# GPS.net
KiCad netlist of a schematic drawn in Altium Designer
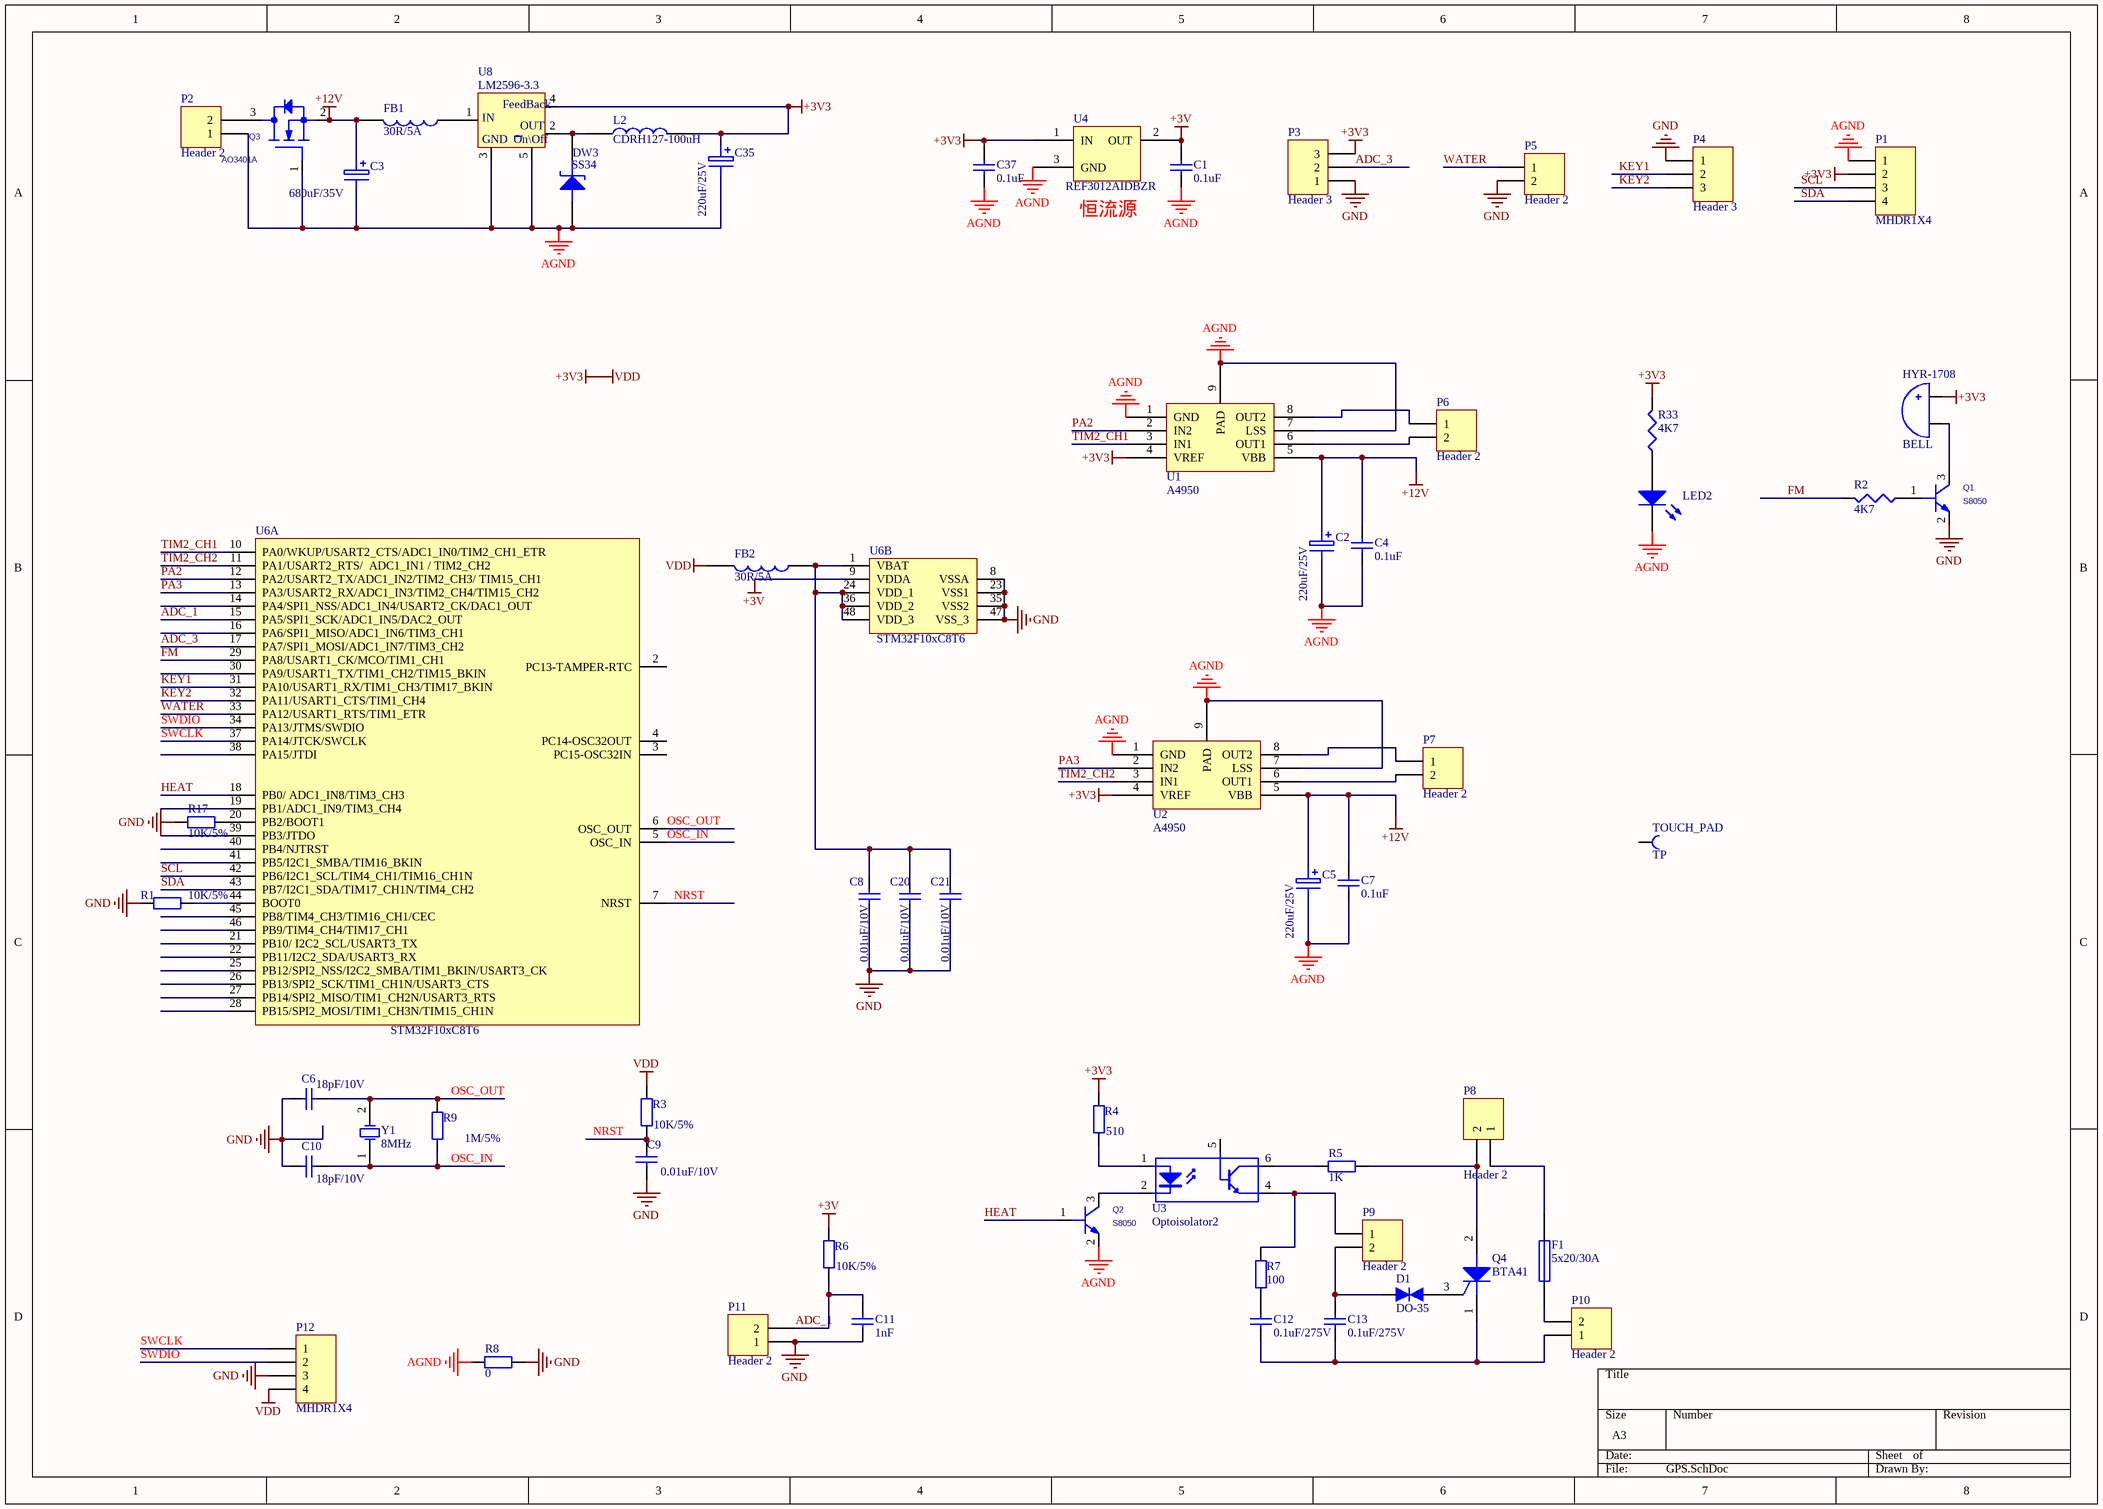
[diagram p0: GPS.SchDoc]

(export (version "E")
  (design (tool "Eeschema 10.0.6"))
  (components
    (comp (ref "C1")
      (value "0.1uF")
      (footprint "0603C")
      (description "Capacitor")
      (fields (field (name "PUBLISHER") "Altium Limited"))
      (libsource (lib "Miscellaneous Devices") (part "Cap"))
    )
    (comp (ref "C2") (value "220uF/25V") (footprint "CAP 2.5*6.3*11.2") (libsource (lib "*") (part "E01")))
    (comp (ref "C3") (value "680uF/35V") (footprint "CAP 5.0*10*16") (libsource (lib "*") (part "E01")))
    (comp (ref "C4")
      (value "0.1uF")
      (footprint "0603C")
      (description "Capacitor")
      (fields (field (name "PUBLISHER") "Altium Limited"))
      (libsource (lib "Miscellaneous Devices") (part "Cap"))
    )
    (comp (ref "C5") (value "220uF/25V") (footprint "CAP 2.5*6.3*11.2") (libsource (lib "*") (part "E01")))
    (comp (ref "C6")
      (value "18pF/10V")
      (footprint "0603C")
      (description "Capacitor")
      (fields (field (name "PUBLISHER") "Altium Limited"))
      (libsource (lib "Miscellaneous Devices") (part "Cap"))
    )
    (comp (ref "C7")
      (value "0.1uF")
      (footprint "0603C")
      (description "Capacitor")
      (fields (field (name "PUBLISHER") "Altium Limited"))
      (libsource (lib "Miscellaneous Devices") (part "Cap"))
    )
    (comp (ref "C8")
      (value "0.01uF/10V")
      (footprint "0603C")
      (description "Capacitor")
      (fields (field (name "PUBLISHER") "Altium Limited"))
      (libsource (lib "Miscellaneous Devices") (part "Cap"))
    )
    (comp (ref "C9")
      (value "0.01uF/10V")
      (footprint "0603c")
      (description "Capacitor")
      (fields (field (name "PUBLISHER") "Altium Limited"))
      (libsource (lib "Miscellaneous Devices") (part "Cap"))
    )
    (comp (ref "C10")
      (value "18pF/10V")
      (footprint "0603c")
      (description "Capacitor")
      (fields (field (name "PUBLISHER") "Altium Limited"))
      (libsource (lib "Miscellaneous Devices") (part "Cap"))
    )
    (comp (ref "C11")
      (value "1nF")
      (footprint "0603C")
      (description "Capacitor")
      (fields (field (name "PUBLISHER") "Altium Limited"))
      (libsource (lib "Miscellaneous Devices") (part "Cap"))
    )
    (comp (ref "C12")
      (value "0.1uF/275V")
      (footprint "CBB 10*12*8")
      (description "Capacitor")
      (fields (field (name "PUBLISHER") "Altium Limited"))
      (libsource (lib "Miscellaneous Devices") (part "Cap"))
    )
    (comp (ref "C13")
      (value "0.1uF/275V")
      (footprint "CBB 10*12*8")
      (description "Capacitor")
      (fields (field (name "PUBLISHER") "Altium Limited"))
      (libsource (lib "Miscellaneous Devices") (part "Cap"))
    )
    (comp (ref "C20")
      (value "0.01uF/10V")
      (footprint "0603C")
      (description "Capacitor")
      (fields (field (name "PUBLISHER") "Altium Limited"))
      (libsource (lib "Miscellaneous Devices") (part "Cap"))
    )
    (comp (ref "C21")
      (value "0.01uF/10V")
      (footprint "0603C")
      (description "Capacitor")
      (fields (field (name "PUBLISHER") "Altium Limited"))
      (libsource (lib "Miscellaneous Devices") (part "Cap"))
    )
    (comp (ref "C35") (value "220uF/25V") (footprint "CAP 2.5*6.3*11.2") (libsource (lib "*") (part "E01")))
    (comp (ref "C37")
      (value "0.1uF")
      (footprint "0603C")
      (description "Capacitor")
      (fields (field (name "PUBLISHER") "Altium Limited"))
      (libsource (lib "Miscellaneous Devices") (part "Cap"))
    )
    (comp (ref "D1")
      (value "DO-35")
      (footprint "DO-35")
      (libsource (lib "Schlib_20110825") (part "ESD9M5.0S-DTVS105"))
    )
    (comp (ref "DW3")
      (value "SS34")
      (footprint "SMA")
      (description "Zener Diode")
      (libsource (lib "MySchlib") (part "ZENER2"))
    )
    (comp (ref "F1")
      (value "5x20/30A")
      (footprint "FU BLX-A")
      (description "Fuse")
      (fields (field (name "PUBLISHER") "Altium Limited"))
      (libsource (lib "Miscellaneous Devices") (part "Fuse 1"))
    )
    (comp (ref "FB1") (value "30R/5A") (footprint "L 0805") (libsource (lib "*") (part "INDUCTOR1")))
    (comp (ref "FB2") (value "30R/5A") (footprint "L 0805") (libsource (lib "*") (part "INDUCTOR1")))
    (comp (ref "HYR-1708")
      (value "BELL")
      (footprint "BEEP 5x9x5.5")
      (description "Bell")
      (libsource (lib "*") (part "BELL"))
    )
    (comp (ref "L2") (value "CDRH127-100uH") (footprint "CDRH74") (libsource (lib "*") (part "INDUCTOR1")))
    (comp (ref "LED2")
      (value "~")
      (footprint "LED 0805R")
      (description "Typical INFRARED GaAs LED")
      (fields (field (name "PUBLISHER") "Altium Limited"))
      (libsource (lib "Miscellaneous Devices") (part "LED0"))
    )
    (comp (ref "P1")
      (value "MHDR1X4")
      (footprint "MX 1.25-LS-4P")
      (description "Header, 4-Pin")
      (fields (field (name "PUBLISHER") "Altium Limited"))
      (libsource (lib "Miscellaneous Connectors") (part "MHDR1X4"))
    )
    (comp (ref "P2")
      (value "Header 2")
      (footprint "VH3.96-LI-2P")
      (description "Header, 2-Pin")
      (fields (field (name "PUBLISHER") "Altium Limited"))
      (libsource (lib "Miscellaneous Connectors") (part "Header 2"))
    )
    (comp (ref "P3")
      (value "Header 3")
      (footprint "XH2.54-LI-3P")
      (description "Header, 3-Pin")
      (fields (field (name "PUBLISHER") "Altium Limited"))
      (libsource (lib "") (part "Header 3_1"))
    )
    (comp (ref "P4")
      (value "Header 3")
      (footprint "MX 1.25-LS-3P")
      (description "Header, 3-Pin")
      (fields (field (name "PUBLISHER") "Altium Limited"))
      (libsource (lib "Miscellaneous Connectors") (part "Header 3"))
    )
    (comp (ref "P5")
      (value "Header 2")
      (footprint "PH2.0-LS-2P")
      (description "Header, 2-Pin")
      (fields (field (name "PUBLISHER") "Altium Limited"))
      (libsource (lib "") (part "Header 2_1"))
    )
    (comp (ref "P6")
      (value "Header 2")
      (footprint "XH2.54-LI-2P")
      (description "Header, 2-Pin")
      (fields (field (name "PUBLISHER") "Altium Limited"))
      (libsource (lib "") (part "Header 2_1"))
    )
    (comp (ref "P7")
      (value "Header 2")
      (footprint "XH2.54-LI-2P")
      (description "Header, 2-Pin")
      (fields (field (name "PUBLISHER") "Altium Limited"))
      (libsource (lib "") (part "Header 2_1"))
    )
    (comp (ref "P8")
      (value "Header 2")
      (footprint "KF2EDGK5.08-LI-2P")
      (description "Header, 2-Pin")
      (fields (field (name "PUBLISHER") "Altium Limited"))
      (libsource (lib "") (part "Header 2_1"))
    )
    (comp (ref "P9")
      (value "Header 2")
      (footprint "VH3.96-LI-2P")
      (description "Header, 2-Pin")
      (fields (field (name "PUBLISHER") "Altium Limited"))
      (libsource (lib "") (part "Header 2_1"))
    )
    (comp (ref "P10")
      (value "Header 2")
      (footprint "KF2EDGK5.08-LI-2P")
      (description "Header, 2-Pin")
      (fields (field (name "PUBLISHER") "Altium Limited"))
      (libsource (lib "") (part "Header 2_2"))
    )
    (comp (ref "P11")
      (value "Header 2")
      (footprint "XH2.54-LI-2P")
      (description "Header, 2-Pin")
      (fields (field (name "PUBLISHER") "Altium Limited"))
      (libsource (lib "Miscellaneous Connectors") (part "Header 2"))
    )
    (comp (ref "P12")
      (value "MHDR1X4")
      (footprint "MX 1.25-LS-4P")
      (description "Header, 4-Pin")
      (fields (field (name "PUBLISHER") "Altium Limited"))
      (libsource (lib "Miscellaneous Connectors") (part "MHDR1X4"))
    )
    (comp (ref "Q1") (value "S8050") (footprint "SOT23-3") (libsource (lib "*") (part "2N1069_1")))
    (comp (ref "Q2") (value "S8050") (footprint "SOT23-3") (libsource (lib "*") (part "2N1069_1")))
    (comp (ref "Q3") (value "AO3401A") (footprint "SOT23-3M") (libsource (lib "Ground_Lock") (part "NMOS")))
    (comp (ref "Q4")
      (value "BTA41")
      (footprint "TOP-3")
      (description "Silicon Controlled Rectifier")
      (fields (field (name "PUBLISHER") "Altium Limited"))
      (libsource (lib "Miscellaneous Devices") (part "SCR"))
    )
    (comp (ref "R1")
      (value "10K/5%")
      (footprint "0603r")
      (description "Resistor")
      (fields (field (name "PUBLISHER") "Altium Limited"))
      (libsource (lib "Miscellaneous Devices") (part "Res2"))
    )
    (comp (ref "R2")
      (value "4K7")
      (footprint "0603R")
      (libsource (lib "ZWLIntegrated_Library") (part "RES1"))
    )
    (comp (ref "R3")
      (value "10K/5%")
      (footprint "0603r")
      (description "Resistor")
      (fields (field (name "PUBLISHER") "Altium Limited"))
      (libsource (lib "") (part "Res2_1"))
    )
    (comp (ref "R4")
      (value "510")
      (footprint "0603r")
      (description "Resistor")
      (fields (field (name "PUBLISHER") "Altium Limited"))
      (libsource (lib "") (part "Res2_1"))
    )
    (comp (ref "R5")
      (value "1K")
      (footprint "RS 1W")
      (description "Resistor")
      (fields (field (name "PUBLISHER") "Altium Limited"))
      (libsource (lib "Miscellaneous Devices") (part "Res2"))
    )
    (comp (ref "R6")
      (value "10K/5%")
      (footprint "0603r")
      (description "Resistor")
      (fields (field (name "PUBLISHER") "Altium Limited"))
      (libsource (lib "") (part "Res2_1"))
    )
    (comp (ref "R7")
      (value "100")
      (footprint "RS 1W")
      (description "Resistor")
      (fields (field (name "PUBLISHER") "Altium Limited"))
      (libsource (lib "") (part "Res2_2"))
    )
    (comp (ref "R8")
      (value "0")
      (footprint "R 0805_M")
      (description "Resistor")
      (fields (field (name "PUBLISHER") "Altium Limited"))
      (libsource (lib "Miscellaneous Devices") (part "Res2"))
    )
    (comp (ref "R9")
      (value "1M/5%")
      (footprint "0603R")
      (description "Resistor")
      (fields (field (name "PUBLISHER") "Altium Limited"))
      (libsource (lib "") (part "Res2_1"))
    )
    (comp (ref "R17")
      (value "10K/5%")
      (footprint "0603r")
      (description "Resistor")
      (fields (field (name "PUBLISHER") "Altium Limited"))
      (libsource (lib "Miscellaneous Devices") (part "Res2"))
    )
    (comp (ref "R33")
      (value "4K7")
      (footprint "0603R")
      (libsource (lib "ZWLIntegrated_Library") (part "RES1"))
    )
    (comp (ref "TOUCH_PAD")
      (value "TP")
      (footprint "SRP12-34-25-P")
      (description "TEST_3P")
      (libsource (lib "stm32") (part "TOUCH_PAD"))
    )
    (comp (ref "U1")
      (value "A4950")
      (footprint "SOIC_8_EP")
      (libsource (lib "Schlib_20110825") (part "A4950"))
    )
    (comp (ref "U2")
      (value "A4950")
      (footprint "SOIC_8_EP")
      (libsource (lib "Schlib_20110825") (part "A4950"))
    )
    (comp (ref "U3")
      (value "Optoisolator2")
      (footprint "DIP6-300")
      (description "5 Pin Mini Flat Pack Optocoupler")
      (fields (field (name "PUBLISHER") "Altium Limited"))
      (libsource (lib "Miscellaneous Devices") (part "Optoisolator2"))
    )
    (comp (ref "U4")
      (value "REF3012AIDBZR")
      (footprint "SOT23-3N")
      (libsource (lib "Schlib1") (part "REF3012"))
    )
    (comp (ref "U6")
      (value "STM32F10xC8T6")
      (footprint "LQFP48 7X7_N")
      (libsource (lib "Myself_1") (part "STM32F100C8T6"))
    )
    (comp (ref "U8") (value "LM2596-3.3") (footprint "TO263-5A") (libsource (lib "*") (part "LM2576")))
    (comp (ref "Y1")
      (value "8MHz")
      (footprint "OSC 5032-2P")
      (description "Crystal Oscillator")
      (fields (field (name "PUBLISHER") "Altium Limited"))
      (libsource (lib "Miscellaneous Devices") (part "XTAL"))
    )
  )
  (nets
    (net (code "1") (name "+3V") (class "Default")
      (node (ref "C1") (pin "1") (pinfunction "1_1") (pintype "passive"))
      (node (ref "R6") (pin "2") (pinfunction "2_2") (pintype "passive"))
      (node (ref "U4") (pin "2") (pinfunction "OUT_2") (pintype "passive"))
      (node (ref "U6") (pin "9") (pinfunction "VDDA_9") (pintype "passive"))
    )
    (net (code "2") (name "+3V3") (class "Default")
      (node (ref "C35") (pin "1") (pintype "passive"))
      (node (ref "C37") (pin "1") (pinfunction "1_1") (pintype "passive"))
      (node (ref "FB2") (pin "1") (pinfunction "1_1") (pintype "passive"))
      (node (ref "HYR-1708") (pin "1") (pinfunction "A_1") (pintype "passive"))
      (node (ref "L2") (pin "1") (pinfunction "1_1") (pintype "passive"))
      (node (ref "P1") (pin "2") (pinfunction "2_2") (pintype "passive"))
      (node (ref "P12") (pin "4") (pinfunction "4_4") (pintype "passive"))
      (node (ref "P3") (pin "3") (pinfunction "3_3") (pintype "passive"))
      (node (ref "R3") (pin "2") (pinfunction "2_2") (pintype "passive"))
      (node (ref "R33") (pin "2") (pinfunction "2_2") (pintype "passive"))
      (node (ref "R4") (pin "2") (pinfunction "2_2") (pintype "passive"))
      (node (ref "U1") (pin "4") (pinfunction "VREF_4") (pintype "passive"))
      (node (ref "U2") (pin "4") (pinfunction "VREF_4") (pintype "passive"))
      (node (ref "U4") (pin "1") (pinfunction "IN_1") (pintype "passive"))
      (node (ref "U8") (pin "4") (pintype "passive"))
    )
    (net (code "3") (name "+12V") (class "Default")
      (node (ref "C2") (pin "1") (pintype "passive"))
      (node (ref "C3") (pin "1") (pintype "passive"))
      (node (ref "C4") (pin "1") (pinfunction "1_1") (pintype "passive"))
      (node (ref "C5") (pin "1") (pintype "passive"))
      (node (ref "C7") (pin "1") (pinfunction "1_1") (pintype "passive"))
      (node (ref "FB1") (pin "1") (pinfunction "1_1") (pintype "passive"))
      (node (ref "Q3") (pin "2") (pinfunction "SOURCE_2") (pintype "passive"))
      (node (ref "U1") (pin "5") (pinfunction "VBB_5") (pintype "passive"))
      (node (ref "U2") (pin "5") (pinfunction "VBB_5") (pintype "passive"))
    )
    (net (code "4") (name "/ADC_1") (class "Default")
      (node (ref "C11") (pin "1") (pinfunction "1_1") (pintype "passive"))
      (node (ref "P11") (pin "2") (pinfunction "2_2") (pintype "passive"))
      (node (ref "R6") (pin "1") (pinfunction "1_1") (pintype "passive"))
      (node (ref "U6") (pin "15") (pinfunction "PA5/SPI1_SCK/ADC1_IN5/DAC2_OUT_15") (pintype "passive"))
    )
    (net (code "5") (name "/ADC_3") (class "Default")
      (node (ref "P3") (pin "2") (pinfunction "2_2") (pintype "passive"))
      (node (ref "U6") (pin "17") (pinfunction "PA7/SPI1_MOSI/ADC1_IN7/TIM3_CH2_17") (pintype "passive"))
    )
    (net (code "6") (name "/FM") (class "Default")
      (node (ref "R2") (pin "2") (pinfunction "2_2") (pintype "passive"))
      (node (ref "U6") (pin "29") (pinfunction "PA8/USART1_CK/MCO/TIM1_CH1_29") (pintype "passive"))
    )
    (net (code "7") (name "/HEAT") (class "Default")
      (node (ref "Q2") (pin "1") (pinfunction "B_1") (pintype "passive"))
      (node (ref "U6") (pin "18") (pinfunction "PB0/_ADC1_IN8/TIM3_CH3_18") (pintype "passive"))
    )
    (net (code "8") (name "/KEY1") (class "Default")
      (node (ref "P4") (pin "2") (pinfunction "2_2") (pintype "passive"))
      (node (ref "U6") (pin "31") (pinfunction "PA10/USART1_RX/TIM1_CH3/TIM17_BKIN_31") (pintype "passive"))
    )
    (net (code "9") (name "/KEY2") (class "Default")
      (node (ref "P4") (pin "3") (pinfunction "3_3") (pintype "passive"))
      (node (ref "U6") (pin "32") (pinfunction "PA11/USART1_CTS/TIM1_CH4_32") (pintype "passive"))
    )
    (net (code "10") (name "/NRST") (class "Default")
      (node (ref "C9") (pin "2") (pinfunction "2_2") (pintype "passive"))
      (node (ref "R3") (pin "1") (pinfunction "1_1") (pintype "passive"))
      (node (ref "U6") (pin "7") (pinfunction "NRST_7") (pintype "passive"))
    )
    (net (code "11") (name "/OSC_IN") (class "Default")
      (node (ref "C10") (pin "2") (pinfunction "2_2") (pintype "passive"))
      (node (ref "R9") (pin "1") (pinfunction "1_1") (pintype "passive"))
      (node (ref "U6") (pin "5") (pinfunction "OSC_IN_5") (pintype "passive"))
      (node (ref "Y1") (pin "1") (pinfunction "OSC1_1") (pintype "passive"))
    )
    (net (code "12") (name "/OSC_OUT") (class "Default")
      (node (ref "C6") (pin "2") (pinfunction "2_2") (pintype "passive"))
      (node (ref "R9") (pin "2") (pinfunction "2_2") (pintype "passive"))
      (node (ref "U6") (pin "6") (pinfunction "OSC_OUT_6") (pintype "passive"))
      (node (ref "Y1") (pin "2") (pinfunction "OSC2_2") (pintype "passive"))
    )
    (net (code "13") (name "/PA2") (class "Default")
      (node (ref "U1") (pin "2") (pinfunction "IN2_2") (pintype "passive"))
      (node (ref "U6") (pin "12") (pinfunction "PA2/USART2_TX/ADC1_IN2/TIM2_CH3/_TIM15_CH1_12") (pintype "passive"))
    )
    (net (code "14") (name "/PA3") (class "Default")
      (node (ref "U2") (pin "2") (pinfunction "IN2_2") (pintype "passive"))
      (node (ref "U6") (pin "13") (pinfunction "PA3/USART2_RX/ADC1_IN3/TIM2_CH4/TIM15_CH2_13") (pintype "passive"))
    )
    (net (code "15") (name "/SCL") (class "Default")
      (node (ref "P1") (pin "3") (pinfunction "3_3") (pintype "passive"))
      (node (ref "U6") (pin "42") (pinfunction "PB6/I2C1_SCL/TIM4_CH1/TIM16_CH1N_42") (pintype "passive"))
    )
    (net (code "16") (name "/SDA") (class "Default")
      (node (ref "P1") (pin "4") (pinfunction "4_4") (pintype "passive"))
      (node (ref "U6") (pin "43") (pinfunction "PB7/I2C1_SDA/TIM17_CH1N/TIM4_CH2_43") (pintype "passive"))
    )
    (net (code "17") (name "/SWCLK") (class "Default")
      (node (ref "P12") (pin "1") (pinfunction "1_1") (pintype "passive"))
      (node (ref "U6") (pin "37") (pinfunction "PA14/JTCK/SWCLK_37") (pintype "passive"))
    )
    (net (code "18") (name "/SWDIO") (class "Default")
      (node (ref "P12") (pin "2") (pinfunction "2_2") (pintype "passive"))
      (node (ref "U6") (pin "34") (pinfunction "PA13/JTMS/SWDIO_34") (pintype "passive"))
    )
    (net (code "19") (name "/TIM2_CH1") (class "Default")
      (node (ref "U1") (pin "3") (pinfunction "IN1_3") (pintype "passive"))
      (node (ref "U6") (pin "10") (pinfunction "PA0/WKUP/USART2_CTS/ADC1_IN0/TIM2_CH1_ETR_10") (pintype "passive"))
    )
    (net (code "20") (name "/TIM2_CH2") (class "Default")
      (node (ref "U2") (pin "3") (pinfunction "IN1_3") (pintype "passive"))
      (node (ref "U6") (pin "11") (pinfunction "PA1/USART2_RTS/__ADC1_IN1_/_TIM2_CH2_11") (pintype "passive"))
    )
    (net (code "21") (name "/WATER") (class "Default")
      (node (ref "P5") (pin "1") (pinfunction "1_1") (pintype "passive"))
      (node (ref "U6") (pin "33") (pinfunction "PA12/USART1_RTS/TIM1_ETR_33") (pintype "passive"))
    )
    (net (code "22") (name "AGND") (class "Default")
      (node (ref "C1") (pin "2") (pinfunction "2_2") (pintype "passive"))
      (node (ref "C2") (pin "2") (pintype "passive"))
      (node (ref "C3") (pin "2") (pintype "passive"))
      (node (ref "C35") (pin "2") (pintype "passive"))
      (node (ref "C37") (pin "2") (pinfunction "2_2") (pintype "passive"))
      (node (ref "C4") (pin "2") (pinfunction "2_2") (pintype "passive"))
      (node (ref "C5") (pin "2") (pintype "passive"))
      (node (ref "C7") (pin "2") (pinfunction "2_2") (pintype "passive"))
      (node (ref "DW3") (pin "1") (pinfunction "A_1") (pintype "passive"))
      (node (ref "LED2") (pin "2") (pinfunction "K_2") (pintype "passive"))
      (node (ref "P1") (pin "1") (pinfunction "1_1") (pintype "passive"))
      (node (ref "P2") (pin "1") (pinfunction "1_1") (pintype "passive"))
      (node (ref "Q2") (pin "2") (pinfunction "E_2") (pintype "passive"))
      (node (ref "Q3") (pin "1") (pinfunction "GATE_1") (pintype "passive"))
      (node (ref "R8") (pin "2") (pinfunction "2_2") (pintype "passive"))
      (node (ref "U1") (pin "1") (pinfunction "GND_1") (pintype "passive"))
      (node (ref "U1") (pin "7") (pinfunction "LSS_7") (pintype "passive"))
      (node (ref "U1") (pin "9") (pinfunction "PAD_9") (pintype "passive"))
      (node (ref "U2") (pin "1") (pinfunction "GND_1") (pintype "passive"))
      (node (ref "U2") (pin "7") (pinfunction "LSS_7") (pintype "passive"))
      (node (ref "U2") (pin "9") (pinfunction "PAD_9") (pintype "passive"))
      (node (ref "U4") (pin "3") (pinfunction "GND_3") (pintype "passive"))
      (node (ref "U8") (pin "3") (pintype "passive"))
      (node (ref "U8") (pin "5") (pintype "passive"))
    )
    (net (code "23") (name "GND") (class "Default")
      (node (ref "C10") (pin "1") (pinfunction "1_1") (pintype "passive"))
      (node (ref "C11") (pin "2") (pinfunction "2_2") (pintype "passive"))
      (node (ref "C20") (pin "2") (pinfunction "2_2") (pintype "passive"))
      (node (ref "C21") (pin "2") (pinfunction "2_2") (pintype "passive"))
      (node (ref "C6") (pin "1") (pinfunction "1_1") (pintype "passive"))
      (node (ref "C8") (pin "2") (pinfunction "2_2") (pintype "passive"))
      (node (ref "C9") (pin "1") (pinfunction "1_1") (pintype "passive"))
      (node (ref "P11") (pin "1") (pinfunction "1_1") (pintype "passive"))
      (node (ref "P12") (pin "3") (pinfunction "3_3") (pintype "passive"))
      (node (ref "P3") (pin "1") (pinfunction "1_1") (pintype "passive"))
      (node (ref "P4") (pin "1") (pinfunction "1_1") (pintype "passive"))
      (node (ref "P5") (pin "2") (pinfunction "2_2") (pintype "passive"))
      (node (ref "Q1") (pin "2") (pinfunction "E_2") (pintype "passive"))
      (node (ref "R1") (pin "2") (pinfunction "2_2") (pintype "passive"))
      (node (ref "R17") (pin "2") (pinfunction "2_2") (pintype "passive"))
      (node (ref "R8") (pin "1") (pinfunction "1_1") (pintype "passive"))
      (node (ref "U6") (pin "23") (pinfunction "VSS1_23") (pintype "passive"))
      (node (ref "U6") (pin "35") (pinfunction "VSS2_35") (pintype "passive"))
      (node (ref "U6") (pin "47") (pinfunction "VSS_3_47") (pintype "passive"))
      (node (ref "U6") (pin "8") (pinfunction "VSSA_8") (pintype "passive"))
    )
    (net (code "24") (name "Net-(C12-Pad1)") (class "Default")
      (node (ref "C12") (pin "1") (pinfunction "1_1") (pintype "passive"))
      (node (ref "R7") (pin "2") (pinfunction "2_2") (pintype "passive"))
    )
    (net (code "25") (name "Net-(D1-A)") (class "Default")
      (node (ref "C13") (pin "1") (pinfunction "1_1") (pintype "passive"))
      (node (ref "D1") (pin "1") (pinfunction "A_1") (pintype "passive"))
      (node (ref "P9") (pin "2") (pinfunction "2_2") (pintype "passive"))
    )
    (net (code "26") (name "Net-(D1-K)") (class "Default")
      (node (ref "D1") (pin "2") (pinfunction "K_2") (pintype "passive"))
      (node (ref "Q4") (pin "3") (pinfunction "G_3") (pintype "passive"))
    )
    (net (code "27") (name "Net-(DW3-K)") (class "Default")
      (node (ref "DW3") (pin "2") (pinfunction "K_2") (pintype "passive"))
      (node (ref "L2") (pin "2") (pinfunction "2_2") (pintype "passive"))
      (node (ref "U8") (pin "2") (pintype "passive"))
    )
    (net (code "28") (name "Net-(F1-Pad1)") (class "Default")
      (node (ref "F1") (pin "1") (pinfunction "1_1") (pintype "passive"))
      (node (ref "P10") (pin "2") (pinfunction "2_2") (pintype "passive"))
    )
    (net (code "29") (name "Net-(F1-Pad2)") (class "Default")
      (node (ref "F1") (pin "2") (pinfunction "2_2") (pintype "passive"))
      (node (ref "P8") (pin "1") (pinfunction "1_1") (pintype "passive"))
    )
    (net (code "30") (name "Net-(FB1-Pad2)") (class "Default")
      (node (ref "FB1") (pin "2") (pinfunction "2_2") (pintype "passive"))
      (node (ref "U8") (pin "1") (pintype "passive"))
    )
    (net (code "31") (name "Net-(HYR-1708-B)") (class "Default")
      (node (ref "HYR-1708") (pin "2") (pinfunction "B_2") (pintype "passive"))
      (node (ref "Q1") (pin "3") (pinfunction "C_3") (pintype "passive"))
    )
    (net (code "32") (name "Net-(LED2-A)") (class "Default")
      (node (ref "LED2") (pin "1") (pinfunction "A_1") (pintype "passive"))
      (node (ref "R33") (pin "1") (pinfunction "1_1") (pintype "passive"))
    )
    (net (code "33") (name "Net-(Q1-B)") (class "Default")
      (node (ref "Q1") (pin "1") (pinfunction "B_1") (pintype "passive"))
      (node (ref "R2") (pin "1") (pinfunction "1_1") (pintype "passive"))
    )
    (net (code "34") (name "Net-(Q2-C)") (class "Default")
      (node (ref "Q2") (pin "3") (pinfunction "C_3") (pintype "passive"))
      (node (ref "U3") (pin "2") (pinfunction "K_2") (pintype "passive"))
    )
    (net (code "35") (name "Net-(Q3-DRAIN)") (class "Default")
      (node (ref "P2") (pin "2") (pinfunction "2_2") (pintype "passive"))
      (node (ref "Q3") (pin "3") (pinfunction "DRAIN_3") (pintype "passive"))
    )
    (net (code "36") (name "Net-(Q4-A)") (class "Default")
      (node (ref "P8") (pin "2") (pinfunction "2_2") (pintype "passive"))
      (node (ref "Q4") (pin "2") (pinfunction "A_2") (pintype "passive"))
      (node (ref "R5") (pin "1") (pinfunction "1_1") (pintype "passive"))
    )
    (net (code "37") (name "Net-(Q4-K)") (class "Default")
      (node (ref "C12") (pin "2") (pinfunction "2_2") (pintype "passive"))
      (node (ref "C13") (pin "2") (pinfunction "2_2") (pintype "passive"))
      (node (ref "P10") (pin "1") (pinfunction "1_1") (pintype "passive"))
      (node (ref "Q4") (pin "1") (pinfunction "K_1") (pintype "passive"))
    )
    (net (code "38") (name "Net-(U1-OUT1)") (class "Default")
      (node (ref "P6") (pin "2") (pinfunction "2_2") (pintype "passive"))
      (node (ref "U1") (pin "6") (pinfunction "OUT1_6") (pintype "passive"))
    )
    (net (code "39") (name "Net-(U1-OUT2)") (class "Default")
      (node (ref "P6") (pin "1") (pinfunction "1_1") (pintype "passive"))
      (node (ref "U1") (pin "8") (pinfunction "OUT2_8") (pintype "passive"))
    )
    (net (code "40") (name "Net-(U2-OUT1)") (class "Default")
      (node (ref "P7") (pin "2") (pinfunction "2_2") (pintype "passive"))
      (node (ref "U2") (pin "6") (pinfunction "OUT1_6") (pintype "passive"))
    )
    (net (code "41") (name "Net-(U2-OUT2)") (class "Default")
      (node (ref "P7") (pin "1") (pinfunction "1_1") (pintype "passive"))
      (node (ref "U2") (pin "8") (pinfunction "OUT2_8") (pintype "passive"))
    )
    (net (code "42") (name "Net-(U3-A)") (class "Default")
      (node (ref "R4") (pin "1") (pinfunction "1_1") (pintype "passive"))
      (node (ref "U3") (pin "1") (pinfunction "A_1") (pintype "passive"))
    )
    (net (code "43") (name "Net-(U3-C)") (class "Default")
      (node (ref "R5") (pin "2") (pinfunction "2_2") (pintype "passive"))
      (node (ref "U3") (pin "6") (pinfunction "C_6") (pintype "passive"))
    )
    (net (code "44") (name "Net-(U3-E)") (class "Default")
      (node (ref "P9") (pin "1") (pinfunction "1_1") (pintype "passive"))
      (node (ref "R7") (pin "1") (pinfunction "1_1") (pintype "passive"))
      (node (ref "U3") (pin "4") (pinfunction "E_4") (pintype "passive"))
    )
    (net (code "45") (name "Net-(U6A-BOOT0)") (class "Default")
      (node (ref "R1") (pin "1") (pinfunction "1_1") (pintype "passive"))
      (node (ref "U6") (pin "44") (pinfunction "BOOT0_44") (pintype "passive"))
    )
    (net (code "46") (name "Net-(U6A-PB2{slash}BOOT1)") (class "Default")
      (node (ref "R17") (pin "1") (pinfunction "1_1") (pintype "passive"))
      (node (ref "U6") (pin "20") (pinfunction "PB2/BOOT1_20") (pintype "passive"))
    )
    (net (code "47") (name "Net-(U6B-VBAT)") (class "Default")
      (node (ref "C20") (pin "1") (pinfunction "1_1") (pintype "passive"))
      (node (ref "C21") (pin "1") (pinfunction "1_1") (pintype "passive"))
      (node (ref "C8") (pin "1") (pinfunction "1_1") (pintype "passive"))
      (node (ref "FB2") (pin "2") (pinfunction "2_2") (pintype "passive"))
      (node (ref "U6") (pin "1") (pinfunction "VBAT_1") (pintype "passive"))
      (node (ref "U6") (pin "24") (pinfunction "VDD_1_24") (pintype "passive"))
      (node (ref "U6") (pin "36") (pinfunction "VDD_2_36") (pintype "passive"))
      (node (ref "U6") (pin "48") (pinfunction "VDD_3_48") (pintype "passive"))
    )
    (net (code "48") (name "unconnected-(TOUCH_PAD-Pad1)") (class "Default")
      (node (ref "TOUCH_PAD") (pin "1") (pinfunction "1_1") (pintype "passive"))
    )
    (net (code "49") (name "unconnected-(U3-B-Pad5)") (class "Default")
      (node (ref "U3") (pin "5") (pinfunction "B_5") (pintype "passive"))
    )
    (net (code "50") (name "unconnected-(U6A-PA4{slash}SPI1_NSS{slash}ADC1_IN4{slash}USART2_CK{slash}DAC1_OUT-Pad14)") (class "Default")
      (node (ref "U6") (pin "14") (pinfunction "PA4/SPI1_NSS/ADC1_IN4/USART2_CK/DAC1_OUT_14") (pintype "passive"))
    )
    (net (code "51") (name "unconnected-(U6A-PA6{slash}SPI1_MISO{slash}ADC1_IN6{slash}TIM3_CH1-Pad16)") (class "Default")
      (node (ref "U6") (pin "16") (pinfunction "PA6/SPI1_MISO/ADC1_IN6/TIM3_CH1_16") (pintype "passive"))
    )
    (net (code "52") (name "unconnected-(U6A-PA9{slash}USART1_TX{slash}TIM1_CH2{slash}TIM15_BKIN-Pad30)") (class "Default")
      (node (ref "U6") (pin "30") (pinfunction "PA9/USART1_TX/TIM1_CH2/TIM15_BKIN_30") (pintype "passive"))
    )
    (net (code "53") (name "unconnected-(U6A-PA15{slash}JTDI-Pad38)") (class "Default")
      (node (ref "U6") (pin "38") (pinfunction "PA15/JTDI_38") (pintype "passive"))
    )
    (net (code "54") (name "unconnected-(U6A-PB1{slash}ADC1_IN9{slash}TIM3_CH4-Pad19)") (class "Default")
      (node (ref "U6") (pin "19") (pinfunction "PB1/ADC1_IN9/TIM3_CH4_19") (pintype "passive"))
    )
    (net (code "55") (name "unconnected-(U6A-PB3{slash}JTDO-Pad39)") (class "Default")
      (node (ref "U6") (pin "39") (pinfunction "PB3/JTDO_39") (pintype "passive"))
    )
    (net (code "56") (name "unconnected-(U6A-PB4{slash}NJTRST-Pad40)") (class "Default")
      (node (ref "U6") (pin "40") (pinfunction "PB4/NJTRST_40") (pintype "passive"))
    )
    (net (code "57") (name "unconnected-(U6A-PB5{slash}I2C1_SMBA{slash}TIM16_BKIN-Pad41)") (class "Default")
      (node (ref "U6") (pin "41") (pinfunction "PB5/I2C1_SMBA/TIM16_BKIN_41") (pintype "passive"))
    )
    (net (code "58") (name "unconnected-(U6A-PB8{slash}TIM4_CH3{slash}TIM16_CH1{slash}CEC-Pad45)") (class "Default")
      (node (ref "U6") (pin "45") (pinfunction "PB8/TIM4_CH3/TIM16_CH1/CEC_45") (pintype "passive"))
    )
    (net (code "59") (name "unconnected-(U6A-PB9{slash}TIM4_CH4{slash}TIM17_CH1-Pad46)") (class "Default")
      (node (ref "U6") (pin "46") (pinfunction "PB9/TIM4_CH4/TIM17_CH1_46") (pintype "passive"))
    )
    (net (code "60") (name "unconnected-(U6A-PB10{slash}_I2C2_SCL{slash}USART3_TX-Pad21)") (class "Default")
      (node (ref "U6") (pin "21") (pinfunction "PB10/_I2C2_SCL/USART3_TX_21") (pintype "passive"))
    )
    (net (code "61") (name "unconnected-(U6A-PB11{slash}I2C2_SDA{slash}USART3_RX-Pad22)") (class "Default")
      (node (ref "U6") (pin "22") (pinfunction "PB11/I2C2_SDA/USART3_RX_22") (pintype "passive"))
    )
    (net (code "62") (name "unconnected-(U6A-PB12{slash}SPI2_NSS{slash}I2C2_SMBA{slash}TIM1_BKIN{slash}USART3_CK-Pad25)") (class "Default")
      (node (ref "U6") (pin "25") (pinfunction "PB12/SPI2_NSS/I2C2_SMBA/TIM1_BKIN/USART3_CK_25") (pintype "passive"))
    )
    (net (code "63") (name "unconnected-(U6A-PB13{slash}SPI2_SCK{slash}TIM1_CH1N{slash}USART3_CTS-Pad26)") (class "Default")
      (node (ref "U6") (pin "26") (pinfunction "PB13/SPI2_SCK/TIM1_CH1N/USART3_CTS_26") (pintype "passive"))
    )
    (net (code "64") (name "unconnected-(U6A-PB14{slash}SPI2_MISO{slash}TIM1_CH2N{slash}USART3_RTS-Pad27)") (class "Default")
      (node (ref "U6") (pin "27") (pinfunction "PB14/SPI2_MISO/TIM1_CH2N/USART3_RTS_27") (pintype "passive"))
    )
    (net (code "65") (name "unconnected-(U6A-PB15{slash}SPI2_MOSI{slash}TIM1_CH3N{slash}TIM15_CH1N-Pad28)") (class "Default")
      (node (ref "U6") (pin "28") (pinfunction "PB15/SPI2_MOSI/TIM1_CH3N/TIM15_CH1N_28") (pintype "passive"))
    )
    (net (code "66") (name "unconnected-(U6A-PC13-TAMPER-RTC-Pad2)") (class "Default")
      (node (ref "U6") (pin "2") (pinfunction "PC13-TAMPER-RTC_2") (pintype "passive"))
    )
    (net (code "67") (name "unconnected-(U6A-PC14-OSC32OUT-Pad4)") (class "Default")
      (node (ref "U6") (pin "4") (pinfunction "PC14-OSC32OUT_4") (pintype "passive"))
    )
    (net (code "68") (name "unconnected-(U6A-PC15-OSC32IN-Pad3)") (class "Default")
      (node (ref "U6") (pin "3") (pinfunction "PC15-OSC32IN_3") (pintype "passive"))
    )
  )
)
